# 25-KeyBoard.net
KiCad netlist of a schematic drawn in Altium Designer
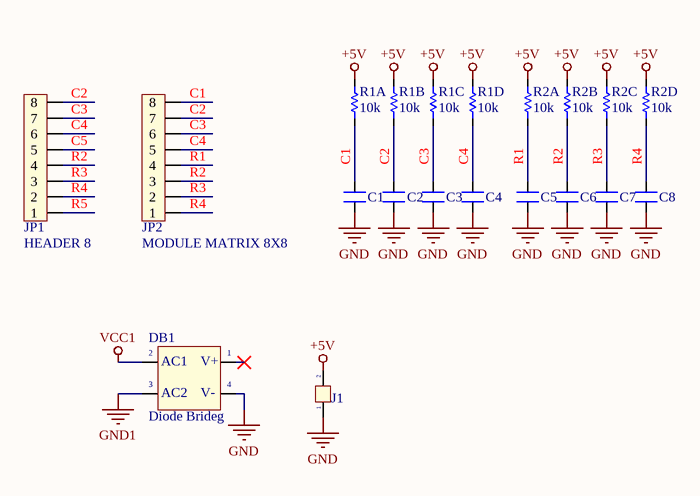
[diagram p0: 25-KeyBoard.SchDoc]

(export (version "E")
  (design (tool "Eeschema 10.0.6"))
  (components
    (comp (ref "C1")
      (value "104")
      (footprint "C-0805")
      (fields (field (name "DESIGNED BY") "VanDungEvn"))
      (libsource (lib "syhaunguyen") (part "CN"))
    )
    (comp (ref "C2")
      (value "104")
      (footprint "C-0805")
      (fields (field (name "DESIGNED BY") "VanDungEvn"))
      (libsource (lib "syhaunguyen") (part "CN"))
    )
    (comp (ref "C3")
      (value "104")
      (footprint "C-0805")
      (fields (field (name "DESIGNED BY") "VanDungEvn"))
      (libsource (lib "syhaunguyen") (part "CN"))
    )
    (comp (ref "C4")
      (value "104")
      (footprint "C-0805")
      (fields (field (name "DESIGNED BY") "VanDungEvn"))
      (libsource (lib "syhaunguyen") (part "CN"))
    )
    (comp (ref "C5")
      (value "104")
      (footprint "C-0805")
      (fields (field (name "DESIGNED BY") "VanDungEvn"))
      (libsource (lib "syhaunguyen") (part "CN"))
    )
    (comp (ref "C6")
      (value "104")
      (footprint "C-0805")
      (fields (field (name "DESIGNED BY") "VanDungEvn"))
      (libsource (lib "syhaunguyen") (part "CN"))
    )
    (comp (ref "C7")
      (value "104")
      (footprint "C-0805")
      (fields (field (name "DESIGNED BY") "VanDungEvn"))
      (libsource (lib "syhaunguyen") (part "CN"))
    )
    (comp (ref "C8")
      (value "104")
      (footprint "C-0805")
      (fields (field (name "DESIGNED BY") "VanDungEvn"))
      (libsource (lib "syhaunguyen") (part "CN"))
    )
    (comp (ref "DB1")
      (value "Diode Brideg")
      (footprint "D-DB-1A-SMD")
      (description "Convert AC to DC voltage, 4 pin")
      (libsource (lib "PART") (part "DB"))
    )
    (comp (ref "J1") (value "Jumper 2") (footprint "JP2") (libsource (lib "syhaunguyen") (part "JP 2")))
    (comp (ref "JP1")
      (value "HEADER 8")
      (footprint "JP8")
      (description "JP8 PIN")
      (libsource (lib "syhaunguyen") (part "JP8"))
    )
    (comp (ref "JP2")
      (value "MODULE MATRIX 8X8")
      (footprint "JP8")
      (description "JP8 PIN")
      (libsource (lib "syhaunguyen") (part "JP8"))
    )
    (comp (ref "R1")
      (value "10k")
      (footprint "R-Array-0603-4")
      (description "RES ARRAY 4 RES 330 OHM 1206")
      (fields
        (field (name "DIGI-KEY PART NUMBER") "Y9331TR-ND")
        (field (name "MANUFACTURER") "Panasonic Electronic Components")
      )
      (libsource (lib "Dlib") (part "Res Array 4"))
    )
    (comp (ref "R2")
      (value "10k")
      (footprint "R-Array-0603-4")
      (description "RES ARRAY 4 RES 330 OHM 1206")
      (fields
        (field (name "DIGI-KEY PART NUMBER") "Y9331TR-ND")
        (field (name "MANUFACTURER") "Panasonic Electronic Components")
      )
      (libsource (lib "Dlib") (part "Res Array 4"))
    )
  )
  (nets
    (net (code "1") (name "+5V") (class "Default")
      (node (ref "J1") (pin "2") (pinfunction "2_2") (pintype "passive"))
      (node (ref "R1") (pin "2") (pinfunction "2_2") (pintype "passive"))
      (node (ref "R1") (pin "4") (pinfunction "2_4") (pintype "passive"))
      (node (ref "R1") (pin "6") (pinfunction "2_6") (pintype "passive"))
      (node (ref "R1") (pin "8") (pinfunction "2_8") (pintype "passive"))
      (node (ref "R2") (pin "2") (pinfunction "2_2") (pintype "passive"))
      (node (ref "R2") (pin "4") (pinfunction "2_4") (pintype "passive"))
      (node (ref "R2") (pin "6") (pinfunction "2_6") (pintype "passive"))
      (node (ref "R2") (pin "8") (pinfunction "2_8") (pintype "passive"))
    )
    (net (code "2") (name "/C1") (class "Default")
      (node (ref "C1") (pin "2") (pinfunction "2_2") (pintype "passive"))
      (node (ref "JP2") (pin "8") (pinfunction "8_8") (pintype "passive"))
      (node (ref "R1") (pin "1") (pinfunction "1_1") (pintype "passive"))
    )
    (net (code "3") (name "/C2") (class "Default")
      (node (ref "C2") (pin "2") (pinfunction "2_2") (pintype "passive"))
      (node (ref "JP1") (pin "8") (pinfunction "8_8") (pintype "passive"))
      (node (ref "JP2") (pin "7") (pinfunction "7_7") (pintype "passive"))
      (node (ref "R1") (pin "3") (pinfunction "1_3") (pintype "passive"))
    )
    (net (code "4") (name "/C3") (class "Default")
      (node (ref "C3") (pin "2") (pinfunction "2_2") (pintype "passive"))
      (node (ref "JP1") (pin "7") (pinfunction "7_7") (pintype "passive"))
      (node (ref "JP2") (pin "6") (pinfunction "6_6") (pintype "passive"))
      (node (ref "R1") (pin "5") (pinfunction "1_5") (pintype "passive"))
    )
    (net (code "5") (name "/C4") (class "Default")
      (node (ref "C4") (pin "2") (pinfunction "2_2") (pintype "passive"))
      (node (ref "JP1") (pin "6") (pinfunction "6_6") (pintype "passive"))
      (node (ref "JP2") (pin "5") (pinfunction "5_5") (pintype "passive"))
      (node (ref "R1") (pin "7") (pinfunction "1_7") (pintype "passive"))
    )
    (net (code "6") (name "/C5") (class "Default")
      (node (ref "JP1") (pin "5") (pinfunction "5_5") (pintype "passive"))
    )
    (net (code "7") (name "/R1") (class "Default")
      (node (ref "C5") (pin "2") (pinfunction "2_2") (pintype "passive"))
      (node (ref "JP2") (pin "4") (pinfunction "4_4") (pintype "passive"))
      (node (ref "R2") (pin "1") (pinfunction "1_1") (pintype "passive"))
    )
    (net (code "8") (name "/R2") (class "Default")
      (node (ref "C6") (pin "2") (pinfunction "2_2") (pintype "passive"))
      (node (ref "JP1") (pin "4") (pinfunction "4_4") (pintype "passive"))
      (node (ref "JP2") (pin "3") (pinfunction "3_3") (pintype "passive"))
      (node (ref "R2") (pin "3") (pinfunction "1_3") (pintype "passive"))
    )
    (net (code "9") (name "/R3") (class "Default")
      (node (ref "C7") (pin "2") (pinfunction "2_2") (pintype "passive"))
      (node (ref "JP1") (pin "3") (pinfunction "3_3") (pintype "passive"))
      (node (ref "JP2") (pin "2") (pinfunction "2_2") (pintype "passive"))
      (node (ref "R2") (pin "5") (pinfunction "1_5") (pintype "passive"))
    )
    (net (code "10") (name "/R4") (class "Default")
      (node (ref "C8") (pin "2") (pinfunction "2_2") (pintype "passive"))
      (node (ref "JP1") (pin "2") (pinfunction "2_2") (pintype "passive"))
      (node (ref "JP2") (pin "1") (pinfunction "1_1") (pintype "passive"))
      (node (ref "R2") (pin "7") (pinfunction "1_7") (pintype "passive"))
    )
    (net (code "11") (name "/R5") (class "Default")
      (node (ref "JP1") (pin "1") (pinfunction "1_1") (pintype "passive"))
    )
    (net (code "12") (name "GND") (class "Default")
      (node (ref "C1") (pin "1") (pinfunction "1_1") (pintype "passive"))
      (node (ref "C2") (pin "1") (pinfunction "1_1") (pintype "passive"))
      (node (ref "C3") (pin "1") (pinfunction "1_1") (pintype "passive"))
      (node (ref "C4") (pin "1") (pinfunction "1_1") (pintype "passive"))
      (node (ref "C5") (pin "1") (pinfunction "1_1") (pintype "passive"))
      (node (ref "C6") (pin "1") (pinfunction "1_1") (pintype "passive"))
      (node (ref "C7") (pin "1") (pinfunction "1_1") (pintype "passive"))
      (node (ref "C8") (pin "1") (pinfunction "1_1") (pintype "passive"))
      (node (ref "DB1") (pin "4") (pinfunction "-V_OUT_4") (pintype "passive"))
      (node (ref "J1") (pin "1") (pinfunction "1_1") (pintype "passive"))
    )
    (net (code "13") (name "GND1") (class "Default")
      (node (ref "DB1") (pin "1") (pinfunction "+V_OUT_1") (pintype "passive"))
    )
    (net (code "14") (name "VCC1") (class "Default")
      (node (ref "DB1") (pin "2") (pinfunction "AC1_2") (pintype "passive"))
    )
    (net (code "15") (name "unconnected-(DB1-AC2-Pad3)") (class "Default")
      (node (ref "DB1") (pin "3") (pinfunction "AC2_3") (pintype "passive+no_connect"))
    )
  )
)
